# MCLR_AVR.net
KiCad netlist of a schematic drawn in Altium Designer
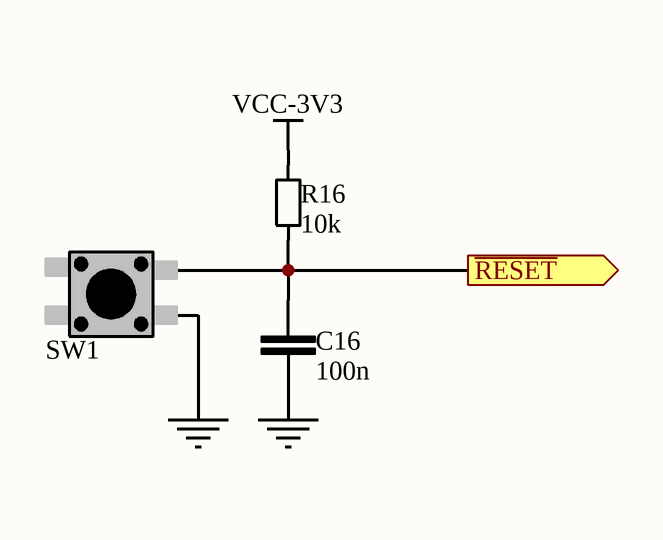
[diagram p0: MCLR_AVR.SchDoc]

(export (version "E")
  (design (tool "Eeschema 10.0.6"))
  (components
    (comp (ref "C16")
      (value "100n")
      (footprint "CER_0603")
      (description "CAP CER 100n 10V X5R 10% 0603")
      (libsource (lib "Capacitors") (part "06032105"))
    )
    (comp (ref "R16")
      (value "10k")
      (footprint "RESC2013X38N-0805-NOOVERLAY")
      (description "RES SMD 10 kOhm 1/8W 0805")
      (libsource (lib "Resistors") (part "000001002"))
    )
    (comp (ref "SW1")
      (value "TASTER")
      (footprint "TASTER_SMD")
      (libsource (lib "Electro_Mechanical") (part "TASTER"))
    )
  )
  (nets
    (net (code "1") (name "/~{RESET}") (class "Default")
      (node (ref "C16") (pin "2") (pinfunction "2_2") (pintype "passive"))
      (node (ref "R16") (pin "1") (pinfunction "1_1") (pintype "passive"))
      (node (ref "SW1") (pin "2") (pinfunction "2_2") (pintype "passive"))
    )
    (net (code "2") (name "GND") (class "Default")
      (node (ref "C16") (pin "1") (pinfunction "1_1") (pintype "passive"))
      (node (ref "SW1") (pin "1") (pinfunction "1_1") (pintype "passive"))
    )
    (net (code "3") (name "VCC-3V3") (class "Default")
      (node (ref "R16") (pin "2") (pinfunction "2_2") (pintype "passive"))
    )
  )
)
